# TPA6133A2.net
KiCad netlist of a schematic drawn in Altium Designer
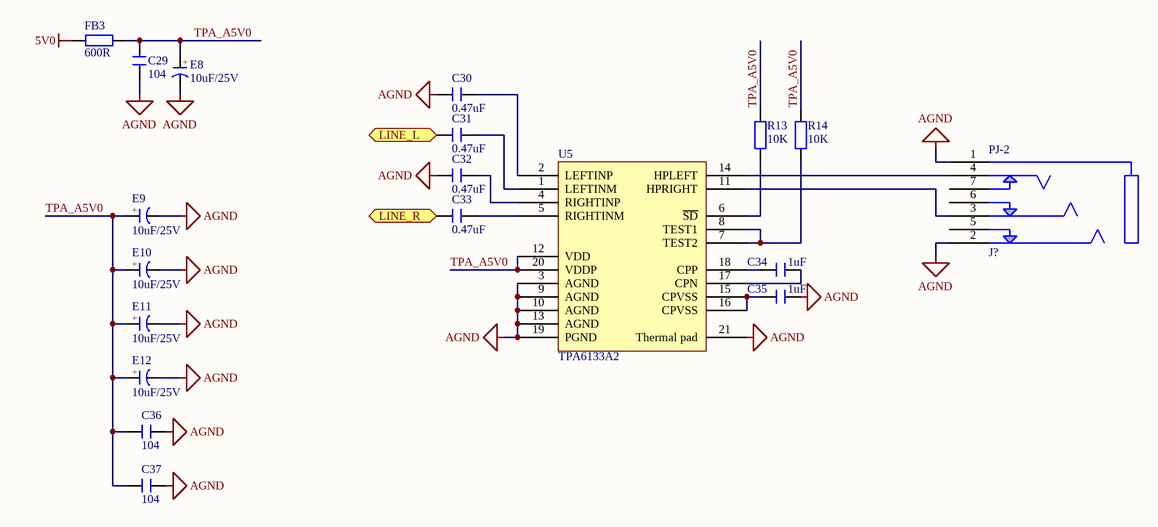
[diagram p0: TPA6133A2.SchDoc]

(export (version "E")
  (design (tool "Eeschema 10.0.6"))
  (components
    (comp (ref "C29")
      (value "104")
      (footprint "C 0603_L")
      (description "贴片电容")
      (libsource (lib "0.1 - 电阻-电容-电感") (part "C"))
    )
    (comp (ref "C30")
      (value "0.47uF")
      (footprint "WIMA 0.47uF")
      (description "贴片电容")
      (libsource (lib "0.1 - 电阻-电容-电感") (part "C"))
    )
    (comp (ref "C31")
      (value "0.47uF")
      (footprint "WIMA 0.47uF")
      (description "贴片电容")
      (libsource (lib "0.1 - 电阻-电容-电感") (part "C"))
    )
    (comp (ref "C32")
      (value "0.47uF")
      (footprint "WIMA 0.47uF")
      (description "贴片电容")
      (libsource (lib "0.1 - 电阻-电容-电感") (part "C"))
    )
    (comp (ref "C33")
      (value "0.47uF")
      (footprint "WIMA 0.47uF")
      (description "贴片电容")
      (libsource (lib "0.1 - 电阻-电容-电感") (part "C"))
    )
    (comp (ref "C34")
      (value "1uF")
      (footprint "C 0603_L")
      (description "贴片电容")
      (libsource (lib "0.1 - 电阻-电容-电感") (part "C"))
    )
    (comp (ref "C35")
      (value "1uF")
      (footprint "C 0603_L")
      (description "贴片电容")
      (libsource (lib "0.1 - 电阻-电容-电感") (part "C"))
    )
    (comp (ref "C36")
      (value "104")
      (footprint "C 0603_L")
      (description "贴片电容")
      (libsource (lib "0.1 - 电阻-电容-电感") (part "C"))
    )
    (comp (ref "C37")
      (value "104")
      (footprint "C 0603_L")
      (description "贴片电容")
      (libsource (lib "0.1 - 电阻-电容-电感") (part "C"))
    )
    (comp (ref "E8")
      (value "10uF/25V")
      (footprint "CD A(3216)")
      (description "贴片钽电容")
      (libsource (lib "") (part "CT_1"))
    )
    (comp (ref "E9")
      (value "10uF/25V")
      (footprint "CD A(3216)")
      (description "贴片钽电容")
      (libsource (lib "0.1 - 电阻-电容-电感") (part "CT"))
    )
    (comp (ref "E10")
      (value "10uF/25V")
      (footprint "CD A(3216)")
      (description "贴片钽电容")
      (libsource (lib "0.1 - 电阻-电容-电感") (part "CT"))
    )
    (comp (ref "E11")
      (value "10uF/25V")
      (footprint "CD A(3216)")
      (description "贴片钽电容")
      (libsource (lib "0.1 - 电阻-电容-电感") (part "CT"))
    )
    (comp (ref "E12")
      (value "10uF/25V")
      (footprint "CD A(3216)")
      (description "贴片钽电容")
      (libsource (lib "0.1 - 电阻-电容-电感") (part "CT"))
    )
    (comp (ref "FB3")
      (value "600R")
      (footprint "R 0805_L")
      (description "贴片电阻")
      (libsource (lib "0.1 - 电阻-电容-电感") (part "R"))
    )
    (comp (ref "PJ-2")
      (value "J?")
      (footprint "PJ-393-7A")
      (description "3.5mm 4段 耳机插座")
      (libsource (lib "音频接口") (part "PJ-393-7"))
    )
    (comp (ref "R13")
      (value "10K")
      (footprint "R 0603_L")
      (description "贴片电阻")
      (libsource (lib "0.1 - 电阻-电容-电感") (part "R"))
    )
    (comp (ref "R14")
      (value "10K")
      (footprint "R 0603_L")
      (description "贴片电阻")
      (libsource (lib "0.1 - 电阻-电容-电感") (part "R"))
    )
    (comp (ref "U5")
      (value "TPA6133A2")
      (footprint "QFN20 4x4_N")
      (libsource (lib "音频芯片") (part "TPA6133A2"))
    )
  )
  (nets
    (net (code "1") (name "/LINE_L") (class "Default")
      (node (ref "C31") (pin "1") (pinfunction "1_1") (pintype "passive"))
    )
    (net (code "2") (name "/LINE_R") (class "Default")
      (node (ref "C33") (pin "1") (pinfunction "1_1") (pintype "passive"))
    )
    (net (code "3") (name "/TPA_A5V0") (class "Default")
      (node (ref "C29") (pin "2") (pinfunction "2_2") (pintype "passive"))
      (node (ref "C36") (pin "2") (pinfunction "2_2") (pintype "passive"))
      (node (ref "C37") (pin "2") (pinfunction "2_2") (pintype "passive"))
      (node (ref "E10") (pin "1") (pinfunction "A_1") (pintype "passive"))
      (node (ref "E11") (pin "1") (pinfunction "A_1") (pintype "passive"))
      (node (ref "E12") (pin "1") (pinfunction "A_1") (pintype "passive"))
      (node (ref "E8") (pin "1") (pinfunction "A_1") (pintype "passive"))
      (node (ref "E9") (pin "1") (pinfunction "A_1") (pintype "passive"))
      (node (ref "FB3") (pin "2") (pinfunction "2_2") (pintype "passive"))
      (node (ref "R13") (pin "1") (pinfunction "1_1") (pintype "passive"))
      (node (ref "R14") (pin "1") (pinfunction "1_1") (pintype "passive"))
      (node (ref "U5") (pin "12") (pinfunction "VDD_12") (pintype "passive"))
      (node (ref "U5") (pin "20") (pinfunction "VDDP_20") (pintype "passive"))
    )
    (net (code "4") (name "5V0") (class "Default")
      (node (ref "FB3") (pin "1") (pinfunction "1_1") (pintype "passive"))
    )
    (net (code "5") (name "AGND") (class "Default")
      (node (ref "C29") (pin "1") (pinfunction "1_1") (pintype "passive"))
      (node (ref "C30") (pin "1") (pinfunction "1_1") (pintype "passive"))
      (node (ref "C32") (pin "1") (pinfunction "1_1") (pintype "passive"))
      (node (ref "C35") (pin "2") (pinfunction "2_2") (pintype "passive"))
      (node (ref "C36") (pin "1") (pinfunction "1_1") (pintype "passive"))
      (node (ref "C37") (pin "1") (pinfunction "1_1") (pintype "passive"))
      (node (ref "E10") (pin "2") (pinfunction "K_2") (pintype "passive"))
      (node (ref "E11") (pin "2") (pinfunction "K_2") (pintype "passive"))
      (node (ref "E12") (pin "2") (pinfunction "K_2") (pintype "passive"))
      (node (ref "E8") (pin "2") (pinfunction "K_2") (pintype "passive"))
      (node (ref "E9") (pin "2") (pinfunction "K_2") (pintype "passive"))
      (node (ref "PJ-2") (pin "1") (pinfunction "1_1") (pintype "passive"))
      (node (ref "PJ-2") (pin "2") (pinfunction "2_2") (pintype "passive"))
      (node (ref "U5") (pin "10") (pinfunction "AGND_10") (pintype "passive"))
      (node (ref "U5") (pin "13") (pinfunction "AGND_13") (pintype "passive"))
      (node (ref "U5") (pin "19") (pinfunction "PGND_19") (pintype "passive"))
      (node (ref "U5") (pin "21") (pinfunction "Thermal_pad_21") (pintype "passive"))
      (node (ref "U5") (pin "3") (pinfunction "AGND_3") (pintype "passive"))
      (node (ref "U5") (pin "9") (pinfunction "AGND_9") (pintype "passive"))
    )
    (net (code "6") (name "Net-(C35-Pad1)") (class "Default")
      (node (ref "C35") (pin "1") (pinfunction "1_1") (pintype "passive"))
      (node (ref "U5") (pin "15") (pinfunction "CPVSS_15") (pintype "passive"))
      (node (ref "U5") (pin "16") (pinfunction "CPVSS_16") (pintype "passive"))
    )
    (net (code "7") (name "Net-(U5-CPN)") (class "Default")
      (node (ref "C34") (pin "2") (pinfunction "2_2") (pintype "passive"))
      (node (ref "U5") (pin "17") (pinfunction "CPN_17") (pintype "passive"))
    )
    (net (code "8") (name "Net-(U5-CPP)") (class "Default")
      (node (ref "C34") (pin "1") (pinfunction "1_1") (pintype "passive"))
      (node (ref "U5") (pin "18") (pinfunction "CPP_18") (pintype "passive"))
    )
    (net (code "9") (name "Net-(U5-HPLEFT)") (class "Default")
      (node (ref "PJ-2") (pin "4") (pinfunction "4_4") (pintype "passive"))
      (node (ref "U5") (pin "14") (pinfunction "HPLEFT_14") (pintype "passive"))
    )
    (net (code "10") (name "Net-(U5-HPRIGHT)") (class "Default")
      (node (ref "PJ-2") (pin "3") (pinfunction "3_3") (pintype "passive"))
      (node (ref "U5") (pin "11") (pinfunction "HPRIGHT_11") (pintype "passive"))
    )
    (net (code "11") (name "Net-(U5-LEFTINM)") (class "Default")
      (node (ref "C31") (pin "2") (pinfunction "2_2") (pintype "passive"))
      (node (ref "U5") (pin "1") (pinfunction "LEFTINM_1") (pintype "passive"))
    )
    (net (code "12") (name "Net-(U5-LEFTINP)") (class "Default")
      (node (ref "C30") (pin "2") (pinfunction "2_2") (pintype "passive"))
      (node (ref "U5") (pin "2") (pinfunction "LEFTINP_2") (pintype "passive"))
    )
    (net (code "13") (name "Net-(U5-RIGHTINM)") (class "Default")
      (node (ref "C33") (pin "2") (pinfunction "2_2") (pintype "passive"))
      (node (ref "U5") (pin "5") (pinfunction "RIGHTINM_5") (pintype "passive"))
    )
    (net (code "14") (name "Net-(U5-RIGHTINP)") (class "Default")
      (node (ref "C32") (pin "2") (pinfunction "2_2") (pintype "passive"))
      (node (ref "U5") (pin "4") (pinfunction "RIGHTINP_4") (pintype "passive"))
    )
    (net (code "15") (name "Net-(U5-TEST1)") (class "Default")
      (node (ref "R14") (pin "2") (pinfunction "2_2") (pintype "passive"))
      (node (ref "U5") (pin "7") (pinfunction "TEST2_7") (pintype "passive"))
      (node (ref "U5") (pin "8") (pinfunction "TEST1_8") (pintype "passive"))
    )
    (net (code "16") (name "Net-(U5-~{SD})") (class "Default")
      (node (ref "R13") (pin "2") (pinfunction "2_2") (pintype "passive"))
      (node (ref "U5") (pin "6") (pinfunction "~{SD}_6") (pintype "passive"))
    )
    (net (code "17") (name "unconnected-(PJ-2-Pad5)") (class "Default")
      (node (ref "PJ-2") (pin "5") (pinfunction "5_5") (pintype "passive"))
    )
    (net (code "18") (name "unconnected-(PJ-2-Pad6)") (class "Default")
      (node (ref "PJ-2") (pin "6") (pinfunction "6_6") (pintype "passive"))
    )
    (net (code "19") (name "unconnected-(PJ-2-Pad7)") (class "Default")
      (node (ref "PJ-2") (pin "7") (pinfunction "7_7") (pintype "passive"))
    )
  )
)
